# 0132-ledz-8.net
KiCad netlist of a schematic drawn in EAGLE
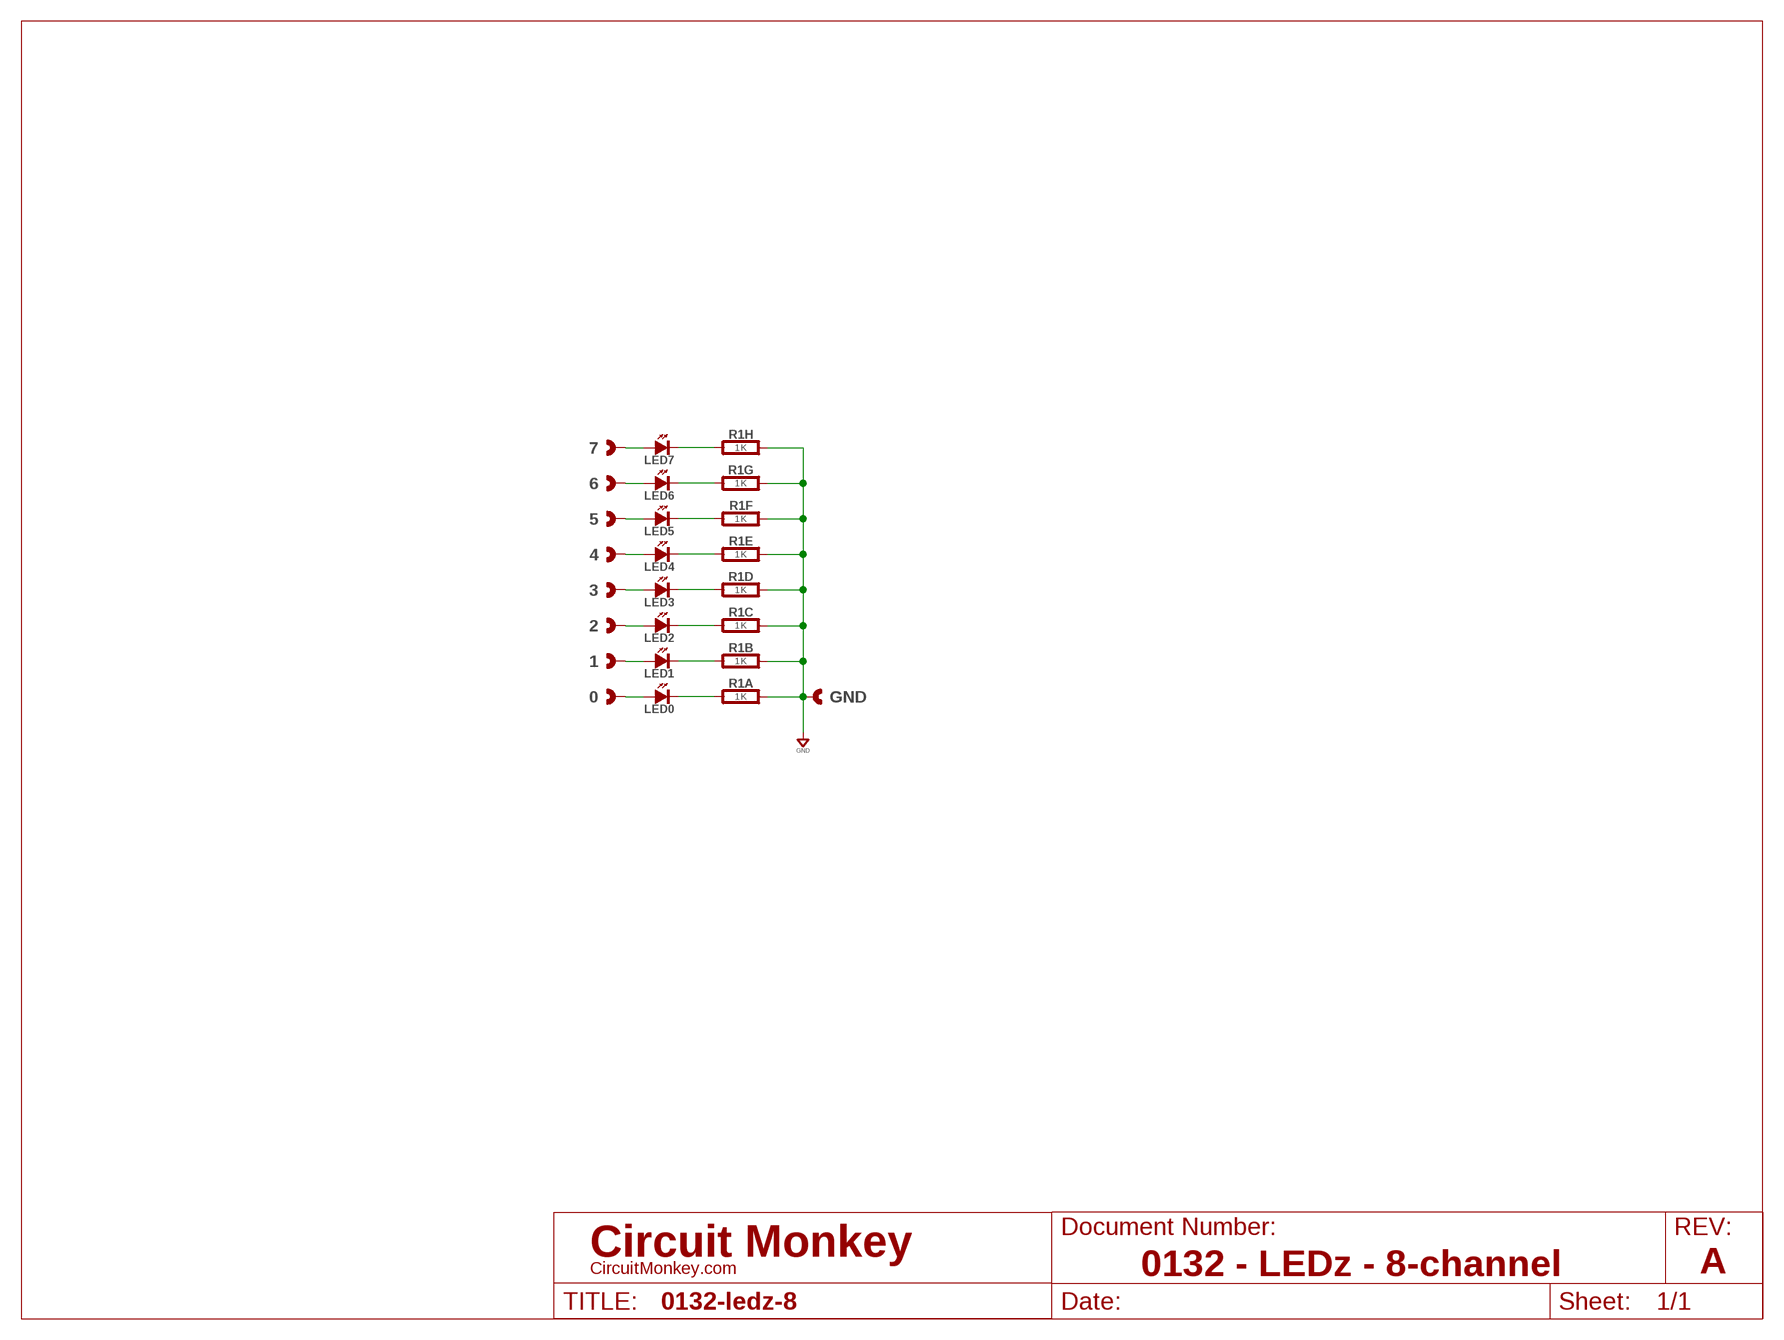
[diagram p0: schematic, sheet 1]

(export (version "E")
  (design (tool "Eeschema 10.0.6"))
  (components
    (comp (ref "0")
      (value "CAST-01X12.00MM")
      (footprint "eagle-import:CAST01-2.00MM")
      (libsource (lib "eagle-import") (part "CAST-01X12.00MM"))
    )
    (comp (ref "1")
      (value "CAST-01X12.00MM")
      (footprint "eagle-import:CAST01-2.00MM")
      (libsource (lib "eagle-import") (part "CAST-01X12.00MM"))
    )
    (comp (ref "2")
      (value "CAST-01X12.00MM")
      (footprint "eagle-import:CAST01-2.00MM")
      (libsource (lib "eagle-import") (part "CAST-01X12.00MM"))
    )
    (comp (ref "3")
      (value "CAST-01X12.00MM")
      (footprint "eagle-import:CAST01-2.00MM")
      (libsource (lib "eagle-import") (part "CAST-01X12.00MM"))
    )
    (comp (ref "4")
      (value "CAST-01X12.00MM")
      (footprint "eagle-import:CAST01-2.00MM")
      (libsource (lib "eagle-import") (part "CAST-01X12.00MM"))
    )
    (comp (ref "5")
      (value "CAST-01X12.00MM")
      (footprint "eagle-import:CAST01-2.00MM")
      (libsource (lib "eagle-import") (part "CAST-01X12.00MM"))
    )
    (comp (ref "6")
      (value "CAST-01X12.00MM")
      (footprint "eagle-import:CAST01-2.00MM")
      (libsource (lib "eagle-import") (part "CAST-01X12.00MM"))
    )
    (comp (ref "7")
      (value "CAST-01X12.00MM")
      (footprint "eagle-import:CAST01-2.00MM")
      (libsource (lib "eagle-import") (part "CAST-01X12.00MM"))
    )
    (comp (ref "GND")
      (value "CAST-01X12.00MM")
      (footprint "eagle-import:CAST01-2.00MM")
      (libsource (lib "eagle-import") (part "CAST-01X12.00MM"))
    )
    (comp (ref "LED0")
      (value "SMT0603")
      (footprint "eagle-import:SMD_0603")
      (libsource (lib "eagle-import") (part "SMT0603"))
    )
    (comp (ref "LED1")
      (value "SMT0603")
      (footprint "eagle-import:SMD_0603")
      (libsource (lib "eagle-import") (part "SMT0603"))
    )
    (comp (ref "LED2")
      (value "SMT0603")
      (footprint "eagle-import:SMD_0603")
      (libsource (lib "eagle-import") (part "SMT0603"))
    )
    (comp (ref "LED3")
      (value "SMT0603")
      (footprint "eagle-import:SMD_0603")
      (libsource (lib "eagle-import") (part "SMT0603"))
    )
    (comp (ref "LED4")
      (value "SMT0603")
      (footprint "eagle-import:SMD_0603")
      (libsource (lib "eagle-import") (part "SMT0603"))
    )
    (comp (ref "LED5")
      (value "SMT0603")
      (footprint "eagle-import:SMD_0603")
      (libsource (lib "eagle-import") (part "SMT0603"))
    )
    (comp (ref "LED6")
      (value "SMT0603")
      (footprint "eagle-import:SMD_0603")
      (libsource (lib "eagle-import") (part "SMT0603"))
    )
    (comp (ref "LED7")
      (value "SMT0603")
      (footprint "eagle-import:SMD_0603")
      (libsource (lib "eagle-import") (part "SMT0603"))
    )
    (comp (ref "R1")
      (value "1K")
      (footprint "eagle-import:RESNET_0402_X8")
      (fields (field (name "MFR") "CTS") (field (name "MPN") "741X163xxx"))
      (libsource (lib "eagle-import") (part "RESNET_0402_INDIV_X8CTS"))
    )
  )
  (nets
    (net (code "1") (name "GND") (class "Default")
      (node (ref "GND") (pin "1") (pinfunction "1_1") (pintype "bidirectional"))
      (node (ref "GND") (pin "P$1") (pinfunction "1_P$1") (pintype "bidirectional"))
      (node (ref "GND") (pin "P$2") (pinfunction "1_P$2") (pintype "bidirectional"))
      (node (ref "R1") (pin "1") (pinfunction "1_1") (pintype "passive"))
      (node (ref "R1") (pin "2") (pinfunction "1_2") (pintype "passive"))
      (node (ref "R1") (pin "3") (pinfunction "1_3") (pintype "passive"))
      (node (ref "R1") (pin "4") (pinfunction "1_4") (pintype "passive"))
      (node (ref "R1") (pin "5") (pinfunction "1_5") (pintype "passive"))
      (node (ref "R1") (pin "6") (pinfunction "1_6") (pintype "passive"))
      (node (ref "R1") (pin "7") (pinfunction "1_7") (pintype "passive"))
      (node (ref "R1") (pin "8") (pinfunction "1_8") (pintype "passive"))
    )
    (net (code "2") (name "Net-(0-1-PadP$1)") (class "Default")
      (node (ref "0") (pin "1") (pinfunction "1_1") (pintype "bidirectional"))
      (node (ref "0") (pin "P$1") (pinfunction "1_P$1") (pintype "bidirectional"))
      (node (ref "0") (pin "P$2") (pinfunction "1_P$2") (pintype "bidirectional"))
      (node (ref "LED0") (pin "A") (pinfunction "A_A") (pintype "passive"))
    )
    (net (code "3") (name "Net-(1-1-PadP$1)") (class "Default")
      (node (ref "1") (pin "1") (pinfunction "1_1") (pintype "bidirectional"))
      (node (ref "1") (pin "P$1") (pinfunction "1_P$1") (pintype "bidirectional"))
      (node (ref "1") (pin "P$2") (pinfunction "1_P$2") (pintype "bidirectional"))
      (node (ref "LED1") (pin "A") (pinfunction "A_A") (pintype "passive"))
    )
    (net (code "4") (name "Net-(2-1-PadP$1)") (class "Default")
      (node (ref "2") (pin "1") (pinfunction "1_1") (pintype "bidirectional"))
      (node (ref "2") (pin "P$1") (pinfunction "1_P$1") (pintype "bidirectional"))
      (node (ref "2") (pin "P$2") (pinfunction "1_P$2") (pintype "bidirectional"))
      (node (ref "LED2") (pin "A") (pinfunction "A_A") (pintype "passive"))
    )
    (net (code "5") (name "Net-(3-1-PadP$1)") (class "Default")
      (node (ref "3") (pin "1") (pinfunction "1_1") (pintype "bidirectional"))
      (node (ref "3") (pin "P$1") (pinfunction "1_P$1") (pintype "bidirectional"))
      (node (ref "3") (pin "P$2") (pinfunction "1_P$2") (pintype "bidirectional"))
      (node (ref "LED3") (pin "A") (pinfunction "A_A") (pintype "passive"))
    )
    (net (code "6") (name "Net-(4-1-PadP$1)") (class "Default")
      (node (ref "4") (pin "1") (pinfunction "1_1") (pintype "bidirectional"))
      (node (ref "4") (pin "P$1") (pinfunction "1_P$1") (pintype "bidirectional"))
      (node (ref "4") (pin "P$2") (pinfunction "1_P$2") (pintype "bidirectional"))
      (node (ref "LED4") (pin "A") (pinfunction "A_A") (pintype "passive"))
    )
    (net (code "7") (name "Net-(5-1-PadP$1)") (class "Default")
      (node (ref "5") (pin "1") (pinfunction "1_1") (pintype "bidirectional"))
      (node (ref "5") (pin "P$1") (pinfunction "1_P$1") (pintype "bidirectional"))
      (node (ref "5") (pin "P$2") (pinfunction "1_P$2") (pintype "bidirectional"))
      (node (ref "LED5") (pin "A") (pinfunction "A_A") (pintype "passive"))
    )
    (net (code "8") (name "Net-(6-1-PadP$1)") (class "Default")
      (node (ref "6") (pin "1") (pinfunction "1_1") (pintype "bidirectional"))
      (node (ref "6") (pin "P$1") (pinfunction "1_P$1") (pintype "bidirectional"))
      (node (ref "6") (pin "P$2") (pinfunction "1_P$2") (pintype "bidirectional"))
      (node (ref "LED6") (pin "A") (pinfunction "A_A") (pintype "passive"))
    )
    (net (code "9") (name "Net-(7-1-PadP$1)") (class "Default")
      (node (ref "7") (pin "1") (pinfunction "1_1") (pintype "bidirectional"))
      (node (ref "7") (pin "P$1") (pinfunction "1_P$1") (pintype "bidirectional"))
      (node (ref "7") (pin "P$2") (pinfunction "1_P$2") (pintype "bidirectional"))
      (node (ref "LED7") (pin "A") (pinfunction "A_A") (pintype "passive"))
    )
    (net (code "10") (name "Net-(LED0-C)") (class "Default")
      (node (ref "LED0") (pin "K") (pinfunction "C_K") (pintype "passive"))
      (node (ref "R1") (pin "16") (pinfunction "2_16") (pintype "passive"))
    )
    (net (code "11") (name "Net-(LED1-C)") (class "Default")
      (node (ref "LED1") (pin "K") (pinfunction "C_K") (pintype "passive"))
      (node (ref "R1") (pin "15") (pinfunction "2_15") (pintype "passive"))
    )
    (net (code "12") (name "Net-(LED2-C)") (class "Default")
      (node (ref "LED2") (pin "K") (pinfunction "C_K") (pintype "passive"))
      (node (ref "R1") (pin "14") (pinfunction "2_14") (pintype "passive"))
    )
    (net (code "13") (name "Net-(LED3-C)") (class "Default")
      (node (ref "LED3") (pin "K") (pinfunction "C_K") (pintype "passive"))
      (node (ref "R1") (pin "13") (pinfunction "2_13") (pintype "passive"))
    )
    (net (code "14") (name "Net-(LED4-C)") (class "Default")
      (node (ref "LED4") (pin "K") (pinfunction "C_K") (pintype "passive"))
      (node (ref "R1") (pin "12") (pinfunction "2_12") (pintype "passive"))
    )
    (net (code "15") (name "Net-(LED5-C)") (class "Default")
      (node (ref "LED5") (pin "K") (pinfunction "C_K") (pintype "passive"))
      (node (ref "R1") (pin "11") (pinfunction "2_11") (pintype "passive"))
    )
    (net (code "16") (name "Net-(LED6-C)") (class "Default")
      (node (ref "LED6") (pin "K") (pinfunction "C_K") (pintype "passive"))
      (node (ref "R1") (pin "10") (pinfunction "2_10") (pintype "passive"))
    )
    (net (code "17") (name "Net-(LED7-C)") (class "Default")
      (node (ref "LED7") (pin "K") (pinfunction "C_K") (pintype "passive"))
      (node (ref "R1") (pin "9") (pinfunction "2_9") (pintype "passive"))
    )
  )
)
